# IRBump.net
KiCad netlist of a schematic drawn in EAGLE
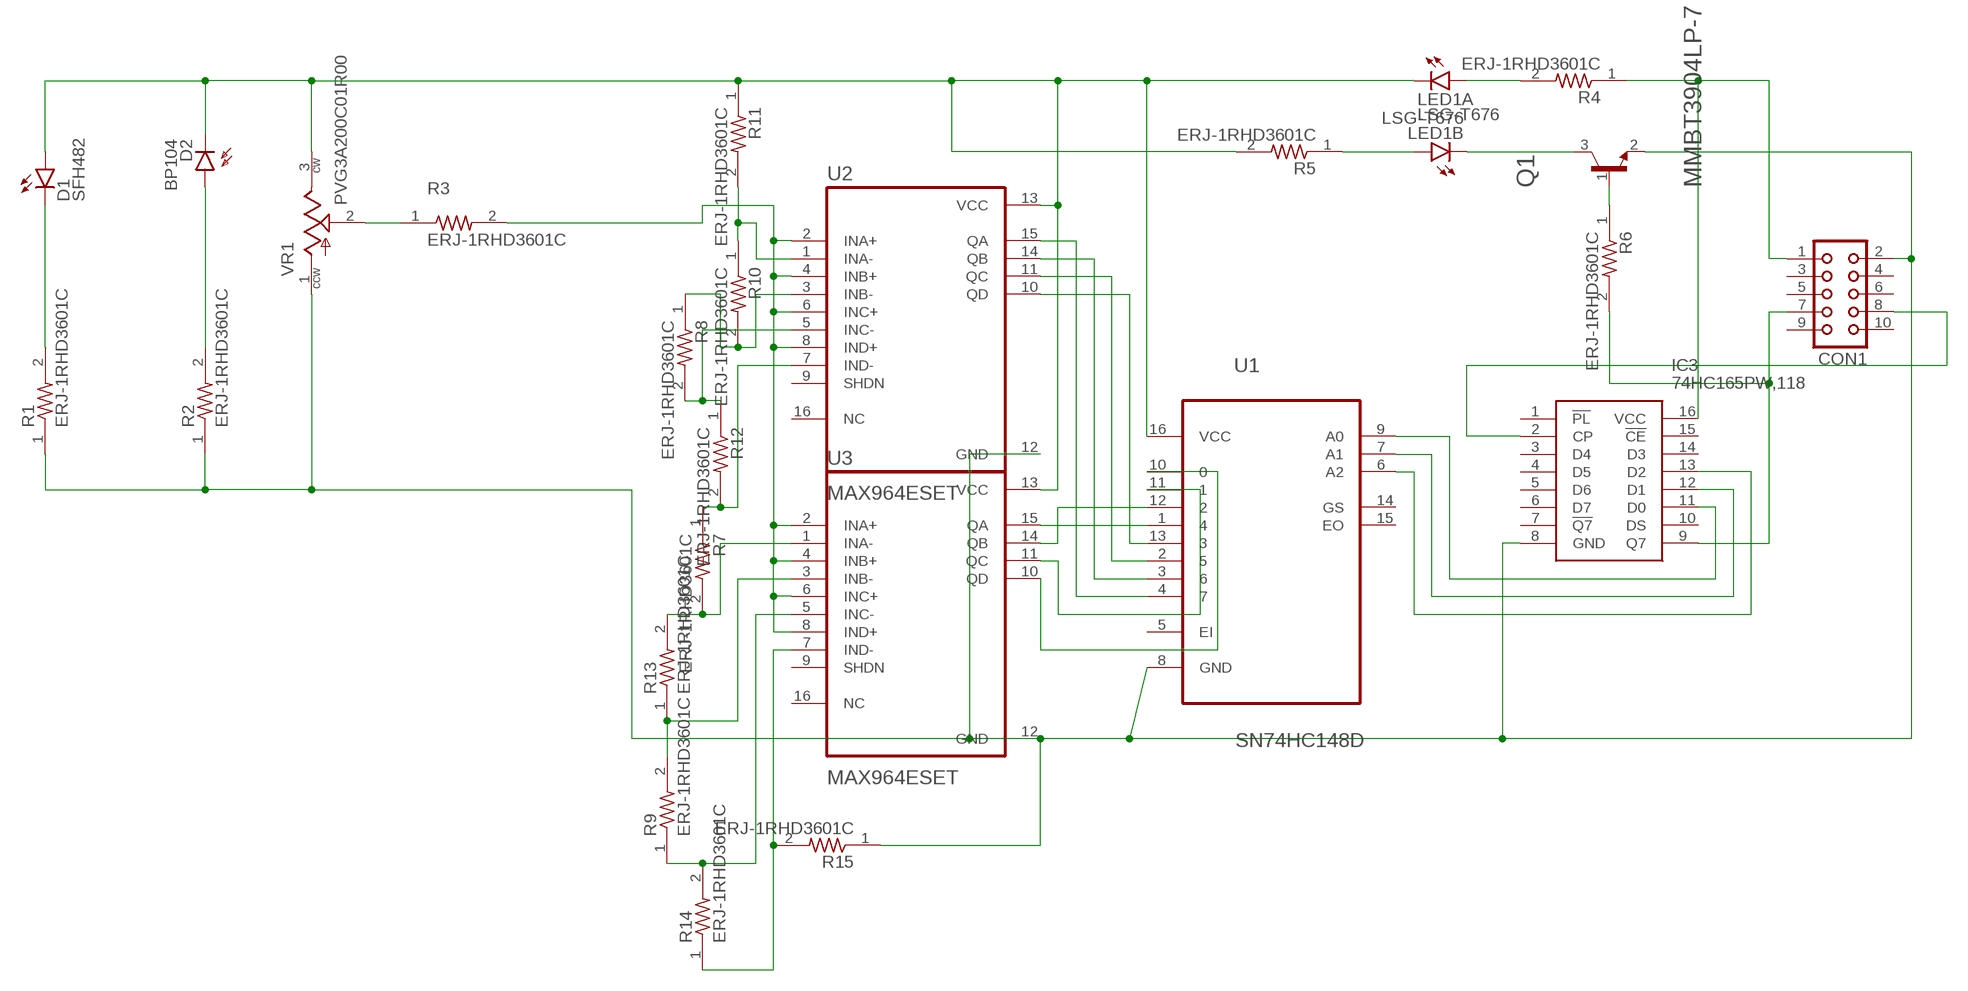
[diagram p0: schematic, sheet 1]

(export (version "E")
  (design (tool "Eeschema 10.0.6"))
  (components
    (comp (ref "CON1")
      (value "CON10")
      (footprint "eagle-import:CON10")
      (libsource (lib "eagle-import") (part "CON10"))
    )
    (comp (ref "D1")
      (value "SFH482")
      (footprint "eagle-import:SFH482")
      (libsource (lib "eagle-import") (part "SFH482"))
    )
    (comp (ref "D2")
      (value "BP104")
      (footprint "eagle-import:BP104")
      (fields (field (name "MF") "VISHAY/TELEFUNKEN"))
      (libsource (lib "eagle-import") (part "BP104"))
    )
    (comp (ref "IC3")
      (value "74HC165PW,118")
      (footprint "eagle-import:SOP65P640X110-16N")
      (fields (field (name "MOUSER_PART_NUMBER") "771-74HC165PW-T"))
      (libsource (lib "eagle-import") (part "74HC165PW,118"))
    )
    (comp (ref "LED1")
      (value "LSG-T676")
      (footprint "eagle-import:P-LCC4-0")
      (libsource (lib "eagle-import") (part "LSG-T676"))
    )
    (comp (ref "Q1")
      (value "MMBT3904LP-7")
      (footprint "eagle-import:DFN101X61X53-3N")
      (fields (field (name "DIGI-KEY_PART_NUMBER") "MMBT3904LP-7DICT-ND") (field (name "MF") "Diodes Inc."))
      (libsource (lib "eagle-import") (part "MMBT3904LP-7"))
    )
    (comp (ref "R1")
      (value "ERJ-1RHD3601C")
      (footprint "eagle-import:RESC0603X26N")
      (fields (field (name "MF") "Panasonic"))
      (libsource (lib "eagle-import") (part "ERJ-1RHD3601C"))
    )
    (comp (ref "R2")
      (value "ERJ-1RHD3601C")
      (footprint "eagle-import:RESC0603X26N")
      (fields (field (name "MF") "Panasonic"))
      (libsource (lib "eagle-import") (part "ERJ-1RHD3601C"))
    )
    (comp (ref "R3")
      (value "ERJ-1RHD3601C")
      (footprint "eagle-import:RESC0603X26N")
      (fields (field (name "MF") "Panasonic"))
      (libsource (lib "eagle-import") (part "ERJ-1RHD3601C"))
    )
    (comp (ref "R4")
      (value "ERJ-1RHD3601C")
      (footprint "eagle-import:RESC0603X26N")
      (fields (field (name "MF") "Panasonic"))
      (libsource (lib "eagle-import") (part "ERJ-1RHD3601C"))
    )
    (comp (ref "R5")
      (value "ERJ-1RHD3601C")
      (footprint "eagle-import:RESC0603X26N")
      (fields (field (name "MF") "Panasonic"))
      (libsource (lib "eagle-import") (part "ERJ-1RHD3601C"))
    )
    (comp (ref "R6")
      (value "ERJ-1RHD3601C")
      (footprint "eagle-import:RESC0603X26N")
      (fields (field (name "MF") "Panasonic"))
      (libsource (lib "eagle-import") (part "ERJ-1RHD3601C"))
    )
    (comp (ref "R7")
      (value "ERJ-1RHD3601C")
      (footprint "eagle-import:RESC0603X26N")
      (fields (field (name "MF") "Panasonic"))
      (libsource (lib "eagle-import") (part "ERJ-1RHD3601C"))
    )
    (comp (ref "R8")
      (value "ERJ-1RHD3601C")
      (footprint "eagle-import:RESC0603X26N")
      (fields (field (name "MF") "Panasonic"))
      (libsource (lib "eagle-import") (part "ERJ-1RHD3601C"))
    )
    (comp (ref "R9")
      (value "ERJ-1RHD3601C")
      (footprint "eagle-import:RESC0603X26N")
      (fields (field (name "MF") "Panasonic"))
      (libsource (lib "eagle-import") (part "ERJ-1RHD3601C"))
    )
    (comp (ref "R10")
      (value "ERJ-1RHD3601C")
      (footprint "eagle-import:RESC0603X26N")
      (fields (field (name "MF") "Panasonic"))
      (libsource (lib "eagle-import") (part "ERJ-1RHD3601C"))
    )
    (comp (ref "R11")
      (value "ERJ-1RHD3601C")
      (footprint "eagle-import:RESC0603X26N")
      (fields (field (name "MF") "Panasonic"))
      (libsource (lib "eagle-import") (part "ERJ-1RHD3601C"))
    )
    (comp (ref "R12")
      (value "ERJ-1RHD3601C")
      (footprint "eagle-import:RESC0603X26N")
      (fields (field (name "MF") "Panasonic"))
      (libsource (lib "eagle-import") (part "ERJ-1RHD3601C"))
    )
    (comp (ref "R13")
      (value "ERJ-1RHD3601C")
      (footprint "eagle-import:RESC0603X26N")
      (fields (field (name "MF") "Panasonic"))
      (libsource (lib "eagle-import") (part "ERJ-1RHD3601C"))
    )
    (comp (ref "R14")
      (value "ERJ-1RHD3601C")
      (footprint "eagle-import:RESC0603X26N")
      (fields (field (name "MF") "Panasonic"))
      (libsource (lib "eagle-import") (part "ERJ-1RHD3601C"))
    )
    (comp (ref "R15")
      (value "ERJ-1RHD3601C")
      (footprint "eagle-import:RESC0603X26N")
      (fields (field (name "MF") "Panasonic"))
      (libsource (lib "eagle-import") (part "ERJ-1RHD3601C"))
    )
    (comp (ref "U1")
      (value "SN74HC148D")
      (footprint "eagle-import:SOIC127P600X175-16N")
      (fields (field (name "MF") "Texas Instruments"))
      (libsource (lib "eagle-import") (part "SN74HC148D"))
    )
    (comp (ref "U2")
      (value "MAX964ESET")
      (footprint "eagle-import:SOIC127P600X175-16N")
      (fields (field (name "MF") "Maxim Integrated") (field (name "MP") "MAX964ESE+"))
      (libsource (lib "eagle-import") (part "MAX964ESET"))
    )
    (comp (ref "U3")
      (value "MAX964ESET")
      (footprint "eagle-import:SOIC127P600X175-16N")
      (fields (field (name "MF") "Maxim Integrated") (field (name "MP") "MAX964ESE+"))
      (libsource (lib "eagle-import") (part "MAX964ESET"))
    )
    (comp (ref "VR1")
      (value "PVG3A200C01R00")
      (footprint "eagle-import:TRIM_PVG3A200C01R00")
      (fields (field (name "MF") "Bourns"))
      (libsource (lib "eagle-import") (part "PVG3A200C01R00"))
    )
  )
  (nets
    (net (code "1") (name "Net-(D1-C)") (class "Default")
      (node (ref "D1") (pin "K") (pinfunction "C_K") (pintype "passive"))
      (node (ref "R1") (pin "2") (pinfunction "2_2") (pintype "passive"))
    )
    (net (code "2") (name "Net-(D2-C)") (class "Default")
      (node (ref "D1") (pin "A") (pinfunction "A_A") (pintype "passive"))
      (node (ref "D2") (pin "K") (pinfunction "C_K") (pintype "passive"))
      (node (ref "LED1") (pin "1") (pinfunction "C_1") (pintype "passive"))
      (node (ref "R11") (pin "1") (pinfunction "1_1") (pintype "passive"))
      (node (ref "R5") (pin "2") (pinfunction "2_2") (pintype "passive"))
      (node (ref "U1") (pin "16") (pinfunction "VCC_16") (pintype "power_in"))
      (node (ref "U2") (pin "13") (pinfunction "VCC_13") (pintype "power_in"))
      (node (ref "U3") (pin "13") (pinfunction "VCC_13") (pintype "power_in"))
      (node (ref "VR1") (pin "3") (pinfunction "CW_3") (pintype "passive"))
    )
    (net (code "3") (name "Net-(D2-PadA)") (class "Default")
      (node (ref "D2") (pin "A") (pinfunction "A_A") (pintype "passive"))
      (node (ref "R2") (pin "2") (pinfunction "2_2") (pintype "passive"))
    )
    (net (code "4") (name "Net-(IC3-CP)") (class "Default")
      (node (ref "CON1") (pin "8") (pinfunction "8_8") (pintype "passive"))
      (node (ref "IC3") (pin "2") (pinfunction "CP_2") (pintype "bidirectional"))
    )
    (net (code "5") (name "Net-(IC3-D0)") (class "Default")
      (node (ref "IC3") (pin "11") (pinfunction "D0_11") (pintype "bidirectional"))
      (node (ref "U1") (pin "9") (pinfunction "A0_9") (pintype "output"))
    )
    (net (code "6") (name "Net-(IC3-D1)") (class "Default")
      (node (ref "IC3") (pin "12") (pinfunction "D1_12") (pintype "bidirectional"))
      (node (ref "U1") (pin "7") (pinfunction "A1_7") (pintype "output"))
    )
    (net (code "7") (name "Net-(IC3-D2)") (class "Default")
      (node (ref "IC3") (pin "13") (pinfunction "D2_13") (pintype "bidirectional"))
      (node (ref "U1") (pin "6") (pinfunction "A2_6") (pintype "output"))
    )
    (net (code "8") (name "Net-(IC3-GND)") (class "Default")
      (node (ref "CON1") (pin "2") (pinfunction "2_2") (pintype "passive"))
      (node (ref "IC3") (pin "8") (pinfunction "GND_8") (pintype "bidirectional"))
      (node (ref "Q1") (pin "2") (pinfunction "E_2") (pintype "passive"))
      (node (ref "R1") (pin "1") (pinfunction "1_1") (pintype "passive"))
      (node (ref "R15") (pin "1") (pinfunction "1_1") (pintype "passive"))
      (node (ref "R2") (pin "1") (pinfunction "1_1") (pintype "passive"))
      (node (ref "U1") (pin "8") (pinfunction "GND_8") (pintype "passive"))
      (node (ref "U2") (pin "12") (pinfunction "GND_12") (pintype "power_in"))
      (node (ref "U3") (pin "12") (pinfunction "GND_12") (pintype "power_in"))
      (node (ref "VR1") (pin "1") (pinfunction "CCW_1") (pintype "passive"))
    )
    (net (code "9") (name "Net-(IC3-Q7)") (class "Default")
      (node (ref "CON1") (pin "7") (pinfunction "7_7") (pintype "passive"))
      (node (ref "IC3") (pin "9") (pinfunction "Q7_9") (pintype "bidirectional"))
      (node (ref "R6") (pin "2") (pinfunction "2_2") (pintype "passive"))
    )
    (net (code "10") (name "Net-(IC3-VCC)") (class "Default")
      (node (ref "CON1") (pin "1") (pinfunction "1_1") (pintype "passive"))
      (node (ref "IC3") (pin "16") (pinfunction "VCC_16") (pintype "bidirectional"))
      (node (ref "R4") (pin "1") (pinfunction "1_1") (pintype "passive"))
    )
    (net (code "11") (name "Net-(LED1A-A)") (class "Default")
      (node (ref "LED1") (pin "2") (pinfunction "A_2") (pintype "passive"))
      (node (ref "R4") (pin "2") (pinfunction "2_2") (pintype "passive"))
    )
    (net (code "12") (name "Net-(LED1B-A)") (class "Default")
      (node (ref "LED1") (pin "4") (pinfunction "A_4") (pintype "passive"))
      (node (ref "R5") (pin "1") (pinfunction "1_1") (pintype "passive"))
    )
    (net (code "13") (name "Net-(LED1B-C)") (class "Default")
      (node (ref "LED1") (pin "3") (pinfunction "C_3") (pintype "passive"))
      (node (ref "Q1") (pin "3") (pinfunction "C_3") (pintype "passive"))
    )
    (net (code "14") (name "Net-(Q1-B)") (class "Default")
      (node (ref "Q1") (pin "1") (pinfunction "B_1") (pintype "passive"))
      (node (ref "R6") (pin "1") (pinfunction "1_1") (pintype "passive"))
    )
    (net (code "15") (name "Net-(U1-0)") (class "Default")
      (node (ref "U1") (pin "10") (pinfunction "0_10") (pintype "input"))
      (node (ref "U3") (pin "10") (pinfunction "QD_10") (pintype "output"))
    )
    (net (code "16") (name "Net-(U1-1)") (class "Default")
      (node (ref "U1") (pin "11") (pinfunction "1_11") (pintype "input"))
      (node (ref "U3") (pin "11") (pinfunction "QC_11") (pintype "output"))
    )
    (net (code "17") (name "Net-(U1-2)") (class "Default")
      (node (ref "U1") (pin "12") (pinfunction "2_12") (pintype "input"))
      (node (ref "U3") (pin "14") (pinfunction "QB_14") (pintype "output"))
    )
    (net (code "18") (name "Net-(U1-3)") (class "Default")
      (node (ref "U1") (pin "13") (pinfunction "3_13") (pintype "input"))
      (node (ref "U2") (pin "10") (pinfunction "QD_10") (pintype "output"))
    )
    (net (code "19") (name "Net-(U1-4)") (class "Default")
      (node (ref "U1") (pin "1") (pinfunction "4_1") (pintype "input"))
      (node (ref "U3") (pin "15") (pinfunction "QA_15") (pintype "output"))
    )
    (net (code "20") (name "Net-(U1-5)") (class "Default")
      (node (ref "U1") (pin "2") (pinfunction "5_2") (pintype "input"))
      (node (ref "U2") (pin "11") (pinfunction "QC_11") (pintype "output"))
    )
    (net (code "21") (name "Net-(U1-6)") (class "Default")
      (node (ref "U1") (pin "3") (pinfunction "6_3") (pintype "input"))
      (node (ref "U2") (pin "14") (pinfunction "QB_14") (pintype "output"))
    )
    (net (code "22") (name "Net-(U1-7)") (class "Default")
      (node (ref "U1") (pin "4") (pinfunction "7_4") (pintype "input"))
      (node (ref "U2") (pin "15") (pinfunction "QA_15") (pintype "output"))
    )
    (net (code "23") (name "Net-(U2-INA+)") (class "Default")
      (node (ref "R3") (pin "2") (pinfunction "2_2") (pintype "passive"))
      (node (ref "U2") (pin "2") (pinfunction "INA+_2") (pintype "input"))
      (node (ref "U2") (pin "4") (pinfunction "INB+_4") (pintype "input"))
      (node (ref "U2") (pin "6") (pinfunction "INC+_6") (pintype "input"))
      (node (ref "U2") (pin "8") (pinfunction "IND+_8") (pintype "input"))
      (node (ref "U3") (pin "2") (pinfunction "INA+_2") (pintype "input"))
      (node (ref "U3") (pin "4") (pinfunction "INB+_4") (pintype "input"))
      (node (ref "U3") (pin "6") (pinfunction "INC+_6") (pintype "input"))
      (node (ref "U3") (pin "8") (pinfunction "IND+_8") (pintype "input"))
    )
    (net (code "24") (name "Net-(U2-INA-)") (class "Default")
      (node (ref "R10") (pin "1") (pinfunction "1_1") (pintype "passive"))
      (node (ref "R11") (pin "2") (pinfunction "2_2") (pintype "passive"))
      (node (ref "U2") (pin "1") (pinfunction "INA-_1") (pintype "input"))
    )
    (net (code "25") (name "Net-(U2-INB-)") (class "Default")
      (node (ref "R10") (pin "2") (pinfunction "2_2") (pintype "passive"))
      (node (ref "R8") (pin "1") (pinfunction "1_1") (pintype "passive"))
      (node (ref "U2") (pin "3") (pinfunction "INB-_3") (pintype "input"))
    )
    (net (code "26") (name "Net-(U2-INC-)") (class "Default")
      (node (ref "R12") (pin "1") (pinfunction "1_1") (pintype "passive"))
      (node (ref "R8") (pin "2") (pinfunction "2_2") (pintype "passive"))
      (node (ref "U2") (pin "5") (pinfunction "INC-_5") (pintype "input"))
    )
    (net (code "27") (name "Net-(U2-IND-)") (class "Default")
      (node (ref "R12") (pin "2") (pinfunction "2_2") (pintype "passive"))
      (node (ref "R7") (pin "1") (pinfunction "1_1") (pintype "passive"))
      (node (ref "U2") (pin "7") (pinfunction "IND-_7") (pintype "input"))
    )
    (net (code "28") (name "Net-(U3-INA-)") (class "Default")
      (node (ref "R13") (pin "2") (pinfunction "2_2") (pintype "passive"))
      (node (ref "R7") (pin "2") (pinfunction "2_2") (pintype "passive"))
      (node (ref "U3") (pin "1") (pinfunction "INA-_1") (pintype "input"))
    )
    (net (code "29") (name "Net-(U3-INB-)") (class "Default")
      (node (ref "R13") (pin "1") (pinfunction "1_1") (pintype "passive"))
      (node (ref "R9") (pin "2") (pinfunction "2_2") (pintype "passive"))
      (node (ref "U3") (pin "3") (pinfunction "INB-_3") (pintype "input"))
    )
    (net (code "30") (name "Net-(U3-INC-)") (class "Default")
      (node (ref "R14") (pin "2") (pinfunction "2_2") (pintype "passive"))
      (node (ref "R9") (pin "1") (pinfunction "1_1") (pintype "passive"))
      (node (ref "U3") (pin "5") (pinfunction "INC-_5") (pintype "input"))
    )
    (net (code "31") (name "Net-(U3-IND-)") (class "Default")
      (node (ref "R14") (pin "1") (pinfunction "1_1") (pintype "passive"))
      (node (ref "R15") (pin "2") (pinfunction "2_2") (pintype "passive"))
      (node (ref "U3") (pin "7") (pinfunction "IND-_7") (pintype "input"))
    )
    (net (code "32") (name "Net-(VR1-WIPER)") (class "Default")
      (node (ref "R3") (pin "1") (pinfunction "1_1") (pintype "passive"))
      (node (ref "VR1") (pin "2") (pinfunction "WIPER_2") (pintype "passive"))
    )
    (net (code "33") (name "unconnected-(CON1-Pad3)") (class "Default")
      (node (ref "CON1") (pin "3") (pinfunction "3_3") (pintype "passive"))
    )
    (net (code "34") (name "unconnected-(CON1-Pad4)") (class "Default")
      (node (ref "CON1") (pin "4") (pinfunction "4_4") (pintype "passive"))
    )
    (net (code "35") (name "unconnected-(CON1-Pad5)") (class "Default")
      (node (ref "CON1") (pin "5") (pinfunction "5_5") (pintype "passive"))
    )
    (net (code "36") (name "unconnected-(CON1-Pad6)") (class "Default")
      (node (ref "CON1") (pin "6") (pinfunction "6_6") (pintype "passive"))
    )
    (net (code "37") (name "unconnected-(CON1-Pad9)") (class "Default")
      (node (ref "CON1") (pin "9") (pinfunction "9_9") (pintype "passive"))
    )
    (net (code "38") (name "unconnected-(CON1-Pad10)") (class "Default")
      (node (ref "CON1") (pin "10") (pinfunction "10_10") (pintype "passive"))
    )
    (net (code "39") (name "unconnected-(IC3-D3-Pad14)") (class "Default")
      (node (ref "IC3") (pin "14") (pinfunction "D3_14") (pintype "bidirectional"))
    )
    (net (code "40") (name "unconnected-(IC3-D4-Pad3)") (class "Default")
      (node (ref "IC3") (pin "3") (pinfunction "D4_3") (pintype "bidirectional"))
    )
    (net (code "41") (name "unconnected-(IC3-D5-Pad4)") (class "Default")
      (node (ref "IC3") (pin "4") (pinfunction "D5_4") (pintype "bidirectional"))
    )
    (net (code "42") (name "unconnected-(IC3-D6-Pad5)") (class "Default")
      (node (ref "IC3") (pin "5") (pinfunction "D6_5") (pintype "bidirectional"))
    )
    (net (code "43") (name "unconnected-(IC3-D7-Pad6)") (class "Default")
      (node (ref "IC3") (pin "6") (pinfunction "D7_6") (pintype "bidirectional"))
    )
    (net (code "44") (name "unconnected-(IC3-DS-Pad10)") (class "Default")
      (node (ref "IC3") (pin "10") (pinfunction "DS_10") (pintype "bidirectional"))
    )
    (net (code "45") (name "unconnected-(IC3-~{CE}-Pad15)") (class "Default")
      (node (ref "IC3") (pin "15") (pinfunction "~{CE}_15") (pintype "bidirectional"))
    )
    (net (code "46") (name "unconnected-(IC3-~{PL}-Pad1)") (class "Default")
      (node (ref "IC3") (pin "1") (pinfunction "~{PL}_1") (pintype "bidirectional"))
    )
    (net (code "47") (name "unconnected-(IC3-~{Q7}-Pad7)") (class "Default")
      (node (ref "IC3") (pin "7") (pinfunction "~{Q7}_7") (pintype "bidirectional"))
    )
    (net (code "48") (name "unconnected-(U1-EI-Pad5)") (class "Default")
      (node (ref "U1") (pin "5") (pinfunction "EI_5") (pintype "input"))
    )
    (net (code "49") (name "unconnected-(U1-EO-Pad15)") (class "Default")
      (node (ref "U1") (pin "15") (pinfunction "EO_15") (pintype "output"))
    )
    (net (code "50") (name "unconnected-(U1-GS-Pad14)") (class "Default")
      (node (ref "U1") (pin "14") (pinfunction "GS_14") (pintype "output"))
    )
    (net (code "51") (name "unconnected-(U2-NC-Pad16)") (class "Default")
      (node (ref "U2") (pin "16") (pinfunction "NC_16") (pintype "bidirectional"))
    )
    (net (code "52") (name "unconnected-(U2-SHDN-Pad9)") (class "Default")
      (node (ref "U2") (pin "9") (pinfunction "SHDN_9") (pintype "input"))
    )
    (net (code "53") (name "unconnected-(U3-NC-Pad16)") (class "Default")
      (node (ref "U3") (pin "16") (pinfunction "NC_16") (pintype "bidirectional"))
    )
    (net (code "54") (name "unconnected-(U3-SHDN-Pad9)") (class "Default")
      (node (ref "U3") (pin "9") (pinfunction "SHDN_9") (pintype "input"))
    )
  )
)
